# FPGA_Bank_66_HP.net
KiCad netlist of a schematic drawn in Altium Designer
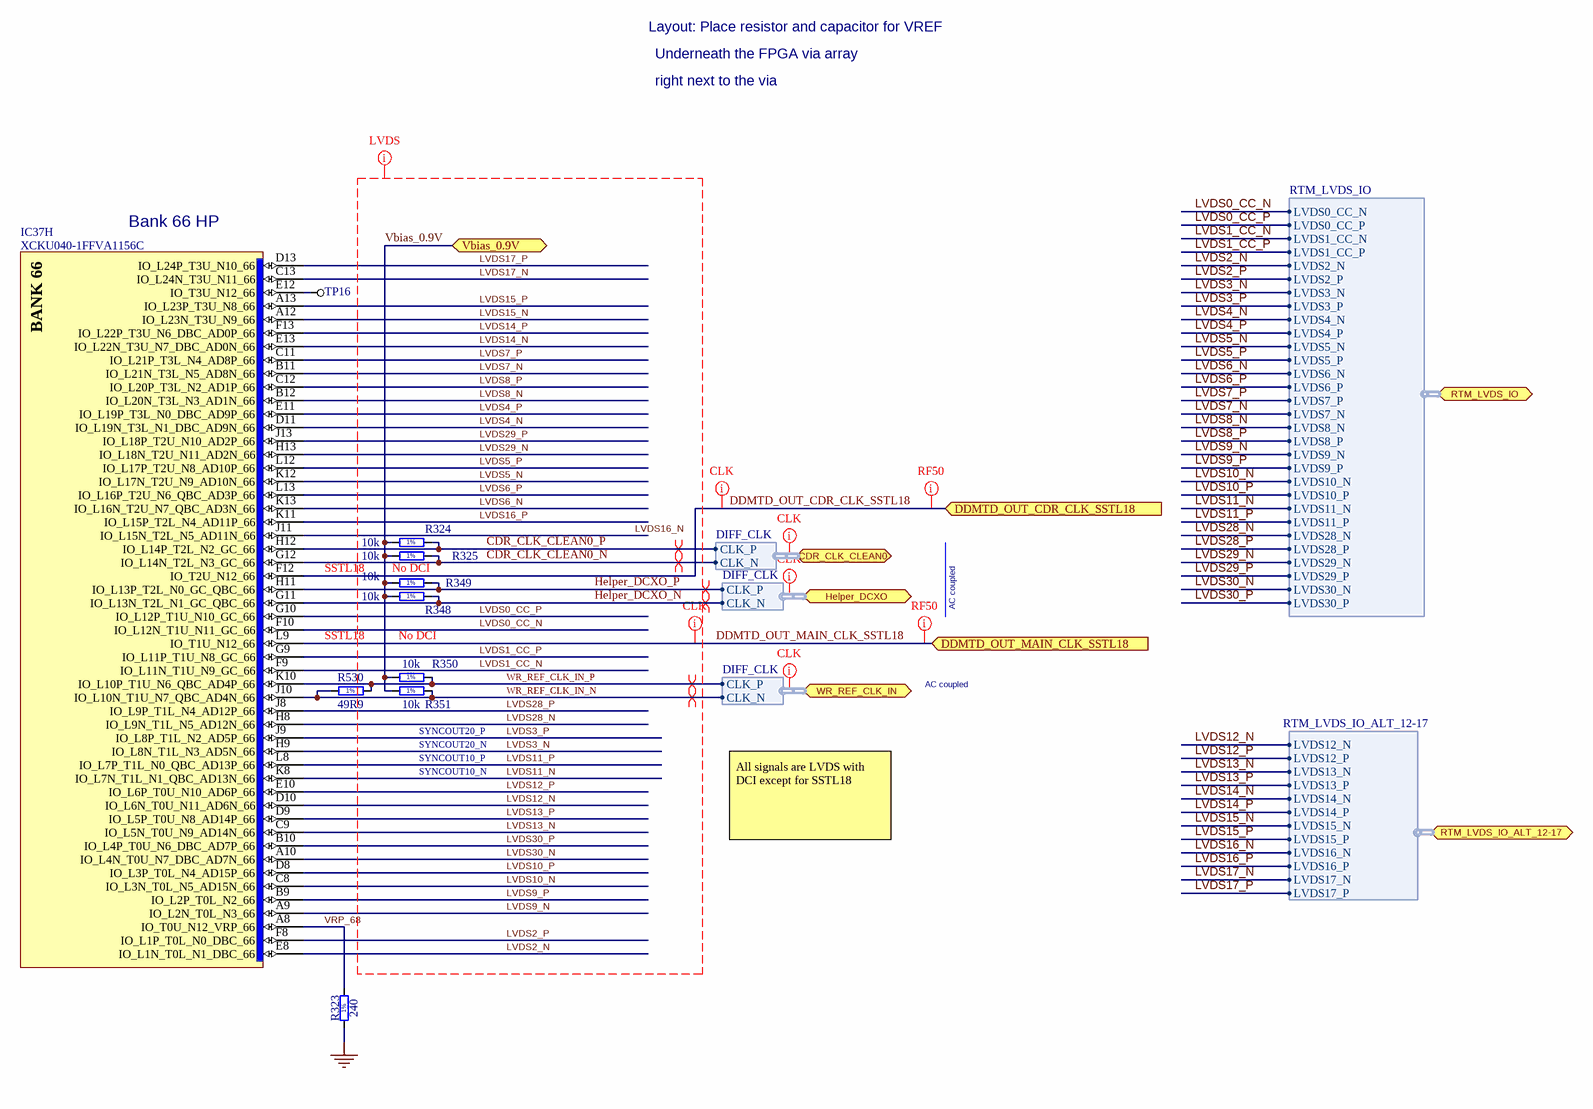
[diagram p0: FPGA_Bank_66_HP.SchDoc]

(export (version "E")
  (design (tool "Eeschema 10.0.6"))
  (components
    (comp (ref "IC37")
      (value "XCKU040-1FFVA1156C")
      (footprint "BGA1156C100P34X34_3500X3500X350")
      (description "Kintex UltraScale FPGA, 520 I/O, 530K Cells, 1156-Ball BGA, Speed Grade 1, Commercial Grade")
      (fields (field (name "MANUFACTURER") "XILINX") (field (name "AUTHOR") "CERN DEM CA"))
      (libsource (lib "ICs And Semiconductors") (part "XCKU040-1FFVA1156C"))
    )
    (comp (ref "R323")
      (value "240")
      (footprint "RESC1005X40N")
      (description "Resistor - 1%")
      (fields
        (field (name "MANUFACTURER PART NUMBER") "R0402_240R_1%_0.0625W_100PPM")
        (field (name "MANUFACTURER") "GENERIC")
        (field (name "AUTHOR") "CERN DEM JLC")
      )
      (libsource (lib "Resistors") (part "Resistor - 1%"))
    )
    (comp (ref "R324")
      (value "10k")
      (footprint "RESC1005X40N")
      (description "Resistor - 1%")
      (fields
        (field (name "MANUFACTURER PART NUMBER") "R0402_10K_1%_0.0625W_100PPM")
        (field (name "MANUFACTURER") "GENERIC")
        (field (name "AUTHOR") "CERN DEM JLC")
      )
      (libsource (lib "Resistors") (part "Resistor - 1%"))
    )
    (comp (ref "R325")
      (value "10k")
      (footprint "RESC1005X40N")
      (description "Resistor - 1%")
      (fields
        (field (name "MANUFACTURER PART NUMBER") "R0402_10K_1%_0.0625W_100PPM")
        (field (name "MANUFACTURER") "GENERIC")
        (field (name "AUTHOR") "CERN DEM JLC")
      )
      (libsource (lib "Resistors") (part "Resistor - 1%"))
    )
    (comp (ref "R348")
      (value "10k")
      (footprint "RESC1005X40N")
      (description "Resistor - 1%")
      (fields
        (field (name "MANUFACTURER PART NUMBER") "R0402_10K_1%_0.0625W_100PPM")
        (field (name "MANUFACTURER") "GENERIC")
        (field (name "AUTHOR") "CERN DEM JLC")
      )
      (libsource (lib "Resistors") (part "Resistor - 1%"))
    )
    (comp (ref "R349")
      (value "10k")
      (footprint "RESC1005X40N")
      (description "Resistor - 1%")
      (fields
        (field (name "MANUFACTURER PART NUMBER") "R0402_10K_1%_0.0625W_100PPM")
        (field (name "MANUFACTURER") "GENERIC")
        (field (name "AUTHOR") "CERN DEM JLC")
      )
      (libsource (lib "Resistors") (part "Resistor - 1%"))
    )
    (comp (ref "R350")
      (value "10k")
      (footprint "RESC1005X40N")
      (description "Resistor - 1%")
      (fields
        (field (name "MANUFACTURER PART NUMBER") "R0402_10K_1%_0.0625W_100PPM")
        (field (name "MANUFACTURER") "GENERIC")
        (field (name "AUTHOR") "CERN DEM JLC")
      )
      (libsource (lib "Resistors") (part "Resistor - 1%"))
    )
    (comp (ref "R351")
      (value "10k")
      (footprint "RESC1005X40N")
      (description "Resistor - 1%")
      (fields
        (field (name "MANUFACTURER PART NUMBER") "R0402_10K_1%_0.0625W_100PPM")
        (field (name "MANUFACTURER") "GENERIC")
        (field (name "AUTHOR") "CERN DEM JLC")
      )
      (libsource (lib "Resistors") (part "Resistor - 1%"))
    )
    (comp (ref "R530")
      (value "49R9")
      (footprint "RESC1005X40N")
      (description "Resistor - 1%")
      (fields
        (field (name "MANUFACTURER PART NUMBER") "R0402_49R9_1%_0.0625W_100PPM")
        (field (name "MANUFACTURER") "GENERIC")
        (field (name "AUTHOR") "CERN DEM JLC")
      )
      (libsource (lib "Resistors") (part "Resistor - 1%"))
    )
    (comp (ref "TP16")
      (value "TP")
      (footprint "TP")
      (description "Testpoint")
      (libsource (lib "LIBRARY_SCH") (part "TP"))
    )
  )
  (nets
    (net (code "4") (name "/CDR_CLK_CLEAN0_N") (class "Default")
      (node (ref "IC37") (pin "G12") (pinfunction "IO_L14N_T2L_N3_GC_66_G12") (pintype "bidirectional"))
      (node (ref "R325") (pin "2") (pinfunction "2_2") (pintype "passive"))
    )
    (net (code "5") (name "/CDR_CLK_CLEAN0_P") (class "Default")
      (node (ref "IC37") (pin "H12") (pinfunction "IO_L14P_T2L_N2_GC_66_H12") (pintype "bidirectional"))
      (node (ref "R324") (pin "2") (pinfunction "2_2") (pintype "passive"))
    )
    (net (code "6") (name "/DDMTD_OUT_CDR_CLK_SSTL18") (class "Default")
      (node (ref "IC37") (pin "F12") (pinfunction "IO_T2U_N12_66_F12") (pintype "bidirectional"))
    )
    (net (code "7") (name "/DDMTD_OUT_MAIN_CLK_SSTL18") (class "Default")
      (node (ref "IC37") (pin "L9") (pinfunction "IO_T1U_N12_66_L9") (pintype "bidirectional"))
    )
    (net (code "8") (name "/Helper_DCXO_N") (class "Default")
      (node (ref "IC37") (pin "G11") (pinfunction "IO_L13N_T2L_N1_GC_QBC_66_G11") (pintype "bidirectional"))
      (node (ref "R349") (pin "2") (pinfunction "2_2") (pintype "passive"))
    )
    (net (code "9") (name "/Helper_DCXO_P") (class "Default")
      (node (ref "IC37") (pin "H11") (pinfunction "IO_L13P_T2L_N0_GC_QBC_66_H11") (pintype "bidirectional"))
      (node (ref "R348") (pin "2") (pinfunction "2_2") (pintype "passive"))
    )
    (net (code "10") (name "/LVDS0_CC_N") (class "Default")
      (node (ref "IC37") (pin "F10") (pinfunction "IO_L12N_T1U_N11_GC_66_F10") (pintype "bidirectional"))
    )
    (net (code "11") (name "/LVDS0_CC_P") (class "Default")
      (node (ref "IC37") (pin "G10") (pinfunction "IO_L12P_T1U_N10_GC_66_G10") (pintype "bidirectional"))
    )
    (net (code "12") (name "/LVDS1_CC_N") (class "Default")
      (node (ref "IC37") (pin "F9") (pinfunction "IO_L11N_T1U_N9_GC_66_F9") (pintype "bidirectional"))
    )
    (net (code "13") (name "/LVDS1_CC_P") (class "Default")
      (node (ref "IC37") (pin "G9") (pinfunction "IO_L11P_T1U_N8_GC_66_G9") (pintype "bidirectional"))
    )
    (net (code "14") (name "/LVDS2_N") (class "Default")
      (node (ref "IC37") (pin "E8") (pinfunction "IO_L1N_T0L_N1_DBC_66_E8") (pintype "bidirectional"))
    )
    (net (code "15") (name "/LVDS2_P") (class "Default")
      (node (ref "IC37") (pin "F8") (pinfunction "IO_L1P_T0L_N0_DBC_66_F8") (pintype "bidirectional"))
    )
    (net (code "16") (name "/LVDS3_N") (class "Default")
      (node (ref "IC37") (pin "H9") (pinfunction "IO_L8N_T1L_N3_AD5N_66_H9") (pintype "bidirectional"))
    )
    (net (code "17") (name "/LVDS3_P") (class "Default")
      (node (ref "IC37") (pin "J9") (pinfunction "IO_L8P_T1L_N2_AD5P_66_J9") (pintype "bidirectional"))
    )
    (net (code "18") (name "/LVDS4_N") (class "Default")
      (node (ref "IC37") (pin "D11") (pinfunction "IO_L19N_T3L_N1_DBC_AD9N_66_D11") (pintype "bidirectional"))
    )
    (net (code "19") (name "/LVDS4_P") (class "Default")
      (node (ref "IC37") (pin "E11") (pinfunction "IO_L19P_T3L_N0_DBC_AD9P_66_E11") (pintype "bidirectional"))
    )
    (net (code "20") (name "/LVDS5_N") (class "Default")
      (node (ref "IC37") (pin "K12") (pinfunction "IO_L17N_T2U_N9_AD10N_66_K12") (pintype "bidirectional"))
    )
    (net (code "21") (name "/LVDS5_P") (class "Default")
      (node (ref "IC37") (pin "L12") (pinfunction "IO_L17P_T2U_N8_AD10P_66_L12") (pintype "bidirectional"))
    )
    (net (code "22") (name "/LVDS6_N") (class "Default")
      (node (ref "IC37") (pin "K13") (pinfunction "IO_L16N_T2U_N7_QBC_AD3N_66_K13") (pintype "bidirectional"))
    )
    (net (code "23") (name "/LVDS6_P") (class "Default")
      (node (ref "IC37") (pin "L13") (pinfunction "IO_L16P_T2U_N6_QBC_AD3P_66_L13") (pintype "bidirectional"))
    )
    (net (code "24") (name "/LVDS7_N") (class "Default")
      (node (ref "IC37") (pin "B11") (pinfunction "IO_L21N_T3L_N5_AD8N_66_B11") (pintype "bidirectional"))
    )
    (net (code "25") (name "/LVDS7_P") (class "Default")
      (node (ref "IC37") (pin "C11") (pinfunction "IO_L21P_T3L_N4_AD8P_66_C11") (pintype "bidirectional"))
    )
    (net (code "26") (name "/LVDS8_N") (class "Default")
      (node (ref "IC37") (pin "B12") (pinfunction "IO_L20N_T3L_N3_AD1N_66_B12") (pintype "bidirectional"))
    )
    (net (code "27") (name "/LVDS8_P") (class "Default")
      (node (ref "IC37") (pin "C12") (pinfunction "IO_L20P_T3L_N2_AD1P_66_C12") (pintype "bidirectional"))
    )
    (net (code "28") (name "/LVDS9_N") (class "Default")
      (node (ref "IC37") (pin "A9") (pinfunction "IO_L2N_T0L_N3_66_A9") (pintype "bidirectional"))
    )
    (net (code "29") (name "/LVDS9_P") (class "Default")
      (node (ref "IC37") (pin "B9") (pinfunction "IO_L2P_T0L_N2_66_B9") (pintype "bidirectional"))
    )
    (net (code "30") (name "/LVDS10_N") (class "Default")
      (node (ref "IC37") (pin "C8") (pinfunction "IO_L3N_T0L_N5_AD15N_66_C8") (pintype "bidirectional"))
    )
    (net (code "31") (name "/LVDS10_P") (class "Default")
      (node (ref "IC37") (pin "D8") (pinfunction "IO_L3P_T0L_N4_AD15P_66_D8") (pintype "bidirectional"))
    )
    (net (code "32") (name "/LVDS11_N") (class "Default")
      (node (ref "IC37") (pin "K8") (pinfunction "IO_L7N_T1L_N1_QBC_AD13N_66_K8") (pintype "bidirectional"))
    )
    (net (code "33") (name "/LVDS11_P") (class "Default")
      (node (ref "IC37") (pin "L8") (pinfunction "IO_L7P_T1L_N0_QBC_AD13P_66_L8") (pintype "bidirectional"))
    )
    (net (code "34") (name "/LVDS12_N") (class "Default")
      (node (ref "IC37") (pin "D10") (pinfunction "IO_L6N_T0U_N11_AD6N_66_D10") (pintype "bidirectional"))
    )
    (net (code "35") (name "/LVDS12_P") (class "Default")
      (node (ref "IC37") (pin "E10") (pinfunction "IO_L6P_T0U_N10_AD6P_66_E10") (pintype "bidirectional"))
    )
    (net (code "36") (name "/LVDS13_N") (class "Default")
      (node (ref "IC37") (pin "C9") (pinfunction "IO_L5N_T0U_N9_AD14N_66_C9") (pintype "bidirectional"))
    )
    (net (code "37") (name "/LVDS13_P") (class "Default")
      (node (ref "IC37") (pin "D9") (pinfunction "IO_L5P_T0U_N8_AD14P_66_D9") (pintype "bidirectional"))
    )
    (net (code "38") (name "/LVDS14_N") (class "Default")
      (node (ref "IC37") (pin "E13") (pinfunction "IO_L22N_T3U_N7_DBC_AD0N_66_E13") (pintype "bidirectional"))
    )
    (net (code "39") (name "/LVDS14_P") (class "Default")
      (node (ref "IC37") (pin "F13") (pinfunction "IO_L22P_T3U_N6_DBC_AD0P_66_F13") (pintype "bidirectional"))
    )
    (net (code "40") (name "/LVDS15_N") (class "Default")
      (node (ref "IC37") (pin "A12") (pinfunction "IO_L23N_T3U_N9_66_A12") (pintype "bidirectional"))
    )
    (net (code "41") (name "/LVDS15_P") (class "Default")
      (node (ref "IC37") (pin "A13") (pinfunction "IO_L23P_T3U_N8_66_A13") (pintype "bidirectional"))
    )
    (net (code "42") (name "/LVDS16_N") (class "Default")
      (node (ref "IC37") (pin "J11") (pinfunction "IO_L15N_T2L_N5_AD11N_66_J11") (pintype "bidirectional"))
    )
    (net (code "43") (name "/LVDS16_P") (class "Default")
      (node (ref "IC37") (pin "K11") (pinfunction "IO_L15P_T2L_N4_AD11P_66_K11") (pintype "bidirectional"))
    )
    (net (code "44") (name "/LVDS17_N") (class "Default")
      (node (ref "IC37") (pin "C13") (pinfunction "IO_L24N_T3U_N11_66_C13") (pintype "bidirectional"))
    )
    (net (code "45") (name "/LVDS17_P") (class "Default")
      (node (ref "IC37") (pin "D13") (pinfunction "IO_L24P_T3U_N10_66_D13") (pintype "bidirectional"))
    )
    (net (code "46") (name "/LVDS28_N") (class "Default")
      (node (ref "IC37") (pin "H8") (pinfunction "IO_L9N_T1L_N5_AD12N_66_H8") (pintype "bidirectional"))
    )
    (net (code "47") (name "/LVDS28_P") (class "Default")
      (node (ref "IC37") (pin "J8") (pinfunction "IO_L9P_T1L_N4_AD12P_66_J8") (pintype "bidirectional"))
    )
    (net (code "48") (name "/LVDS29_N") (class "Default")
      (node (ref "IC37") (pin "H13") (pinfunction "IO_L18N_T2U_N11_AD2N_66_H13") (pintype "bidirectional"))
    )
    (net (code "49") (name "/LVDS29_P") (class "Default")
      (node (ref "IC37") (pin "J13") (pinfunction "IO_L18P_T2U_N10_AD2P_66_J13") (pintype "bidirectional"))
    )
    (net (code "50") (name "/LVDS30_N") (class "Default")
      (node (ref "IC37") (pin "A10") (pinfunction "IO_L4N_T0U_N7_DBC_AD7N_66_A10") (pintype "bidirectional"))
    )
    (net (code "51") (name "/LVDS30_P") (class "Default")
      (node (ref "IC37") (pin "B10") (pinfunction "IO_L4P_T0U_N6_DBC_AD7P_66_B10") (pintype "bidirectional"))
    )
    (net (code "52") (name "/VRP_68") (class "Default")
      (node (ref "IC37") (pin "A8") (pinfunction "IO_T0U_N12_VRP_66_A8") (pintype "bidirectional"))
      (node (ref "R323") (pin "2") (pinfunction "2_2") (pintype "passive"))
    )
    (net (code "53") (name "/Vbias_0.9V") (class "Default")
      (node (ref "R324") (pin "1") (pinfunction "1_1") (pintype "passive"))
      (node (ref "R325") (pin "1") (pinfunction "1_1") (pintype "passive"))
      (node (ref "R348") (pin "1") (pinfunction "1_1") (pintype "passive"))
      (node (ref "R349") (pin "1") (pinfunction "1_1") (pintype "passive"))
      (node (ref "R350") (pin "1") (pinfunction "1_1") (pintype "passive"))
      (node (ref "R351") (pin "1") (pinfunction "1_1") (pintype "passive"))
    )
    (net (code "54") (name "/WR_REF_CLK_IN_N") (class "Default")
      (node (ref "IC37") (pin "J10") (pinfunction "IO_L10N_T1U_N7_QBC_AD4N_66_J10") (pintype "bidirectional"))
      (node (ref "R351") (pin "2") (pinfunction "2_2") (pintype "passive"))
      (node (ref "R530") (pin "1") (pinfunction "1_1") (pintype "passive"))
    )
    (net (code "55") (name "/WR_REF_CLK_IN_P") (class "Default")
      (node (ref "IC37") (pin "K10") (pinfunction "IO_L10P_T1U_N6_QBC_AD4P_66_K10") (pintype "bidirectional"))
      (node (ref "R350") (pin "2") (pinfunction "2_2") (pintype "passive"))
      (node (ref "R530") (pin "2") (pinfunction "2_2") (pintype "passive"))
    )
    (net (code "59") (name "GND") (class "Default")
      (node (ref "R323") (pin "1") (pinfunction "1_1") (pintype "passive"))
    )
    (net (code "60") (name "Net-(IC37H-IO_T3U_N12_66)") (class "Default")
      (node (ref "IC37") (pin "E12") (pinfunction "IO_T3U_N12_66_E12") (pintype "bidirectional"))
      (node (ref "TP16") (pin "1") (pintype "passive"))
    )
  )
)
